# OR_gate.net
KiCad netlist of a schematic drawn in EAGLE
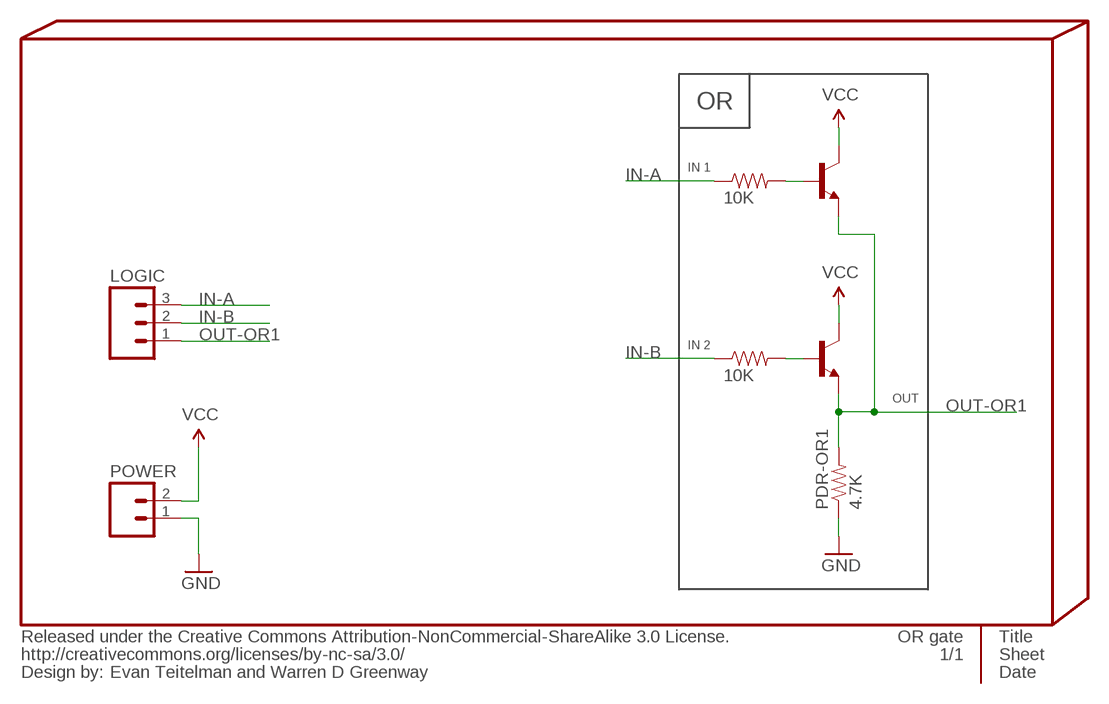
[diagram p0: schematic, sheet 1]

(export (version "E")
  (design (tool "Eeschema 10.0.6"))
  (components
    (comp (ref "INFO4")
      (value "Evan Teitelman and Warren D Greenway")
      (footprint "eagle-import:%CC-NC-SA")
      (libsource (lib "eagle-import") (part "%CC-NC-SA"))
    )
    (comp (ref "LOGIC")
      (value "M03PTH")
      (footprint "eagle-import:1X03")
      (libsource (lib "eagle-import") (part "M03PTH"))
    )
    (comp (ref "PDR-OR1")
      (value "4.7K")
      (footprint "eagle-import:0402-RES")
      (libsource (lib "eagle-import") (part "RESISTOR0402-RES"))
    )
    (comp (ref "POWER")
      (value "M02PTH")
      (footprint "eagle-import:1X02")
      (libsource (lib "eagle-import") (part "M02PTH"))
    )
    (comp (ref "Q1-OR1")
      (value "TRANSISTOR_NPNSOT23")
      (footprint "eagle-import:SOT23")
      (libsource (lib "eagle-import") (part "TRANSISTOR_NPNSOT23"))
    )
    (comp (ref "Q2-OR1")
      (value "TRANSISTOR_NPNSOT23")
      (footprint "eagle-import:SOT23")
      (libsource (lib "eagle-import") (part "TRANSISTOR_NPNSOT23"))
    )
    (comp (ref "R1-OR1")
      (value "10K")
      (footprint "eagle-import:0402-RES")
      (libsource (lib "eagle-import") (part "RESISTOR0402-RES"))
    )
    (comp (ref "R2-OR1")
      (value "10K")
      (footprint "eagle-import:0402-RES")
      (libsource (lib "eagle-import") (part "RESISTOR0402-RES"))
    )
  )
  (nets
    (net (code "1") (name "/IN-A") (class "Default")
      (node (ref "LOGIC") (pin "3") (pinfunction "3_3") (pintype "passive"))
      (node (ref "R1-OR1") (pin "1") (pinfunction "1_1") (pintype "passive"))
    )
    (net (code "2") (name "/IN-B") (class "Default")
      (node (ref "LOGIC") (pin "2") (pinfunction "2_2") (pintype "passive"))
      (node (ref "R2-OR1") (pin "1") (pinfunction "1_1") (pintype "passive"))
    )
    (net (code "3") (name "/OUT-OR1") (class "Default")
      (node (ref "LOGIC") (pin "1") (pinfunction "1_1") (pintype "passive"))
      (node (ref "PDR-OR1") (pin "2") (pinfunction "2_2") (pintype "passive"))
      (node (ref "Q1-OR1") (pin "2") (pinfunction "E_2") (pintype "passive"))
      (node (ref "Q2-OR1") (pin "2") (pinfunction "E_2") (pintype "passive"))
    )
    (net (code "4") (name "@GND") (class "Default")
      (node (ref "PDR-OR1") (pin "1") (pinfunction "1_1") (pintype "passive"))
      (node (ref "POWER") (pin "1") (pinfunction "1_1") (pintype "passive"))
    )
    (net (code "5") (name "@VCC") (class "Default")
      (node (ref "POWER") (pin "2") (pinfunction "2_2") (pintype "passive"))
      (node (ref "Q1-OR1") (pin "3") (pinfunction "C_3") (pintype "passive"))
      (node (ref "Q2-OR1") (pin "3") (pinfunction "C_3") (pintype "passive"))
    )
    (net (code "6") (name "Net-(Q1-OR1-B)") (class "Default")
      (node (ref "Q1-OR1") (pin "1") (pinfunction "B_1") (pintype "passive"))
      (node (ref "R1-OR1") (pin "2") (pinfunction "2_2") (pintype "passive"))
    )
    (net (code "7") (name "Net-(Q2-OR1-B)") (class "Default")
      (node (ref "Q2-OR1") (pin "1") (pinfunction "B_1") (pintype "passive"))
      (node (ref "R2-OR1") (pin "2") (pinfunction "2_2") (pintype "passive"))
    )
  )
)
